# working.net
KiCad netlist of a schematic drawn in EAGLE
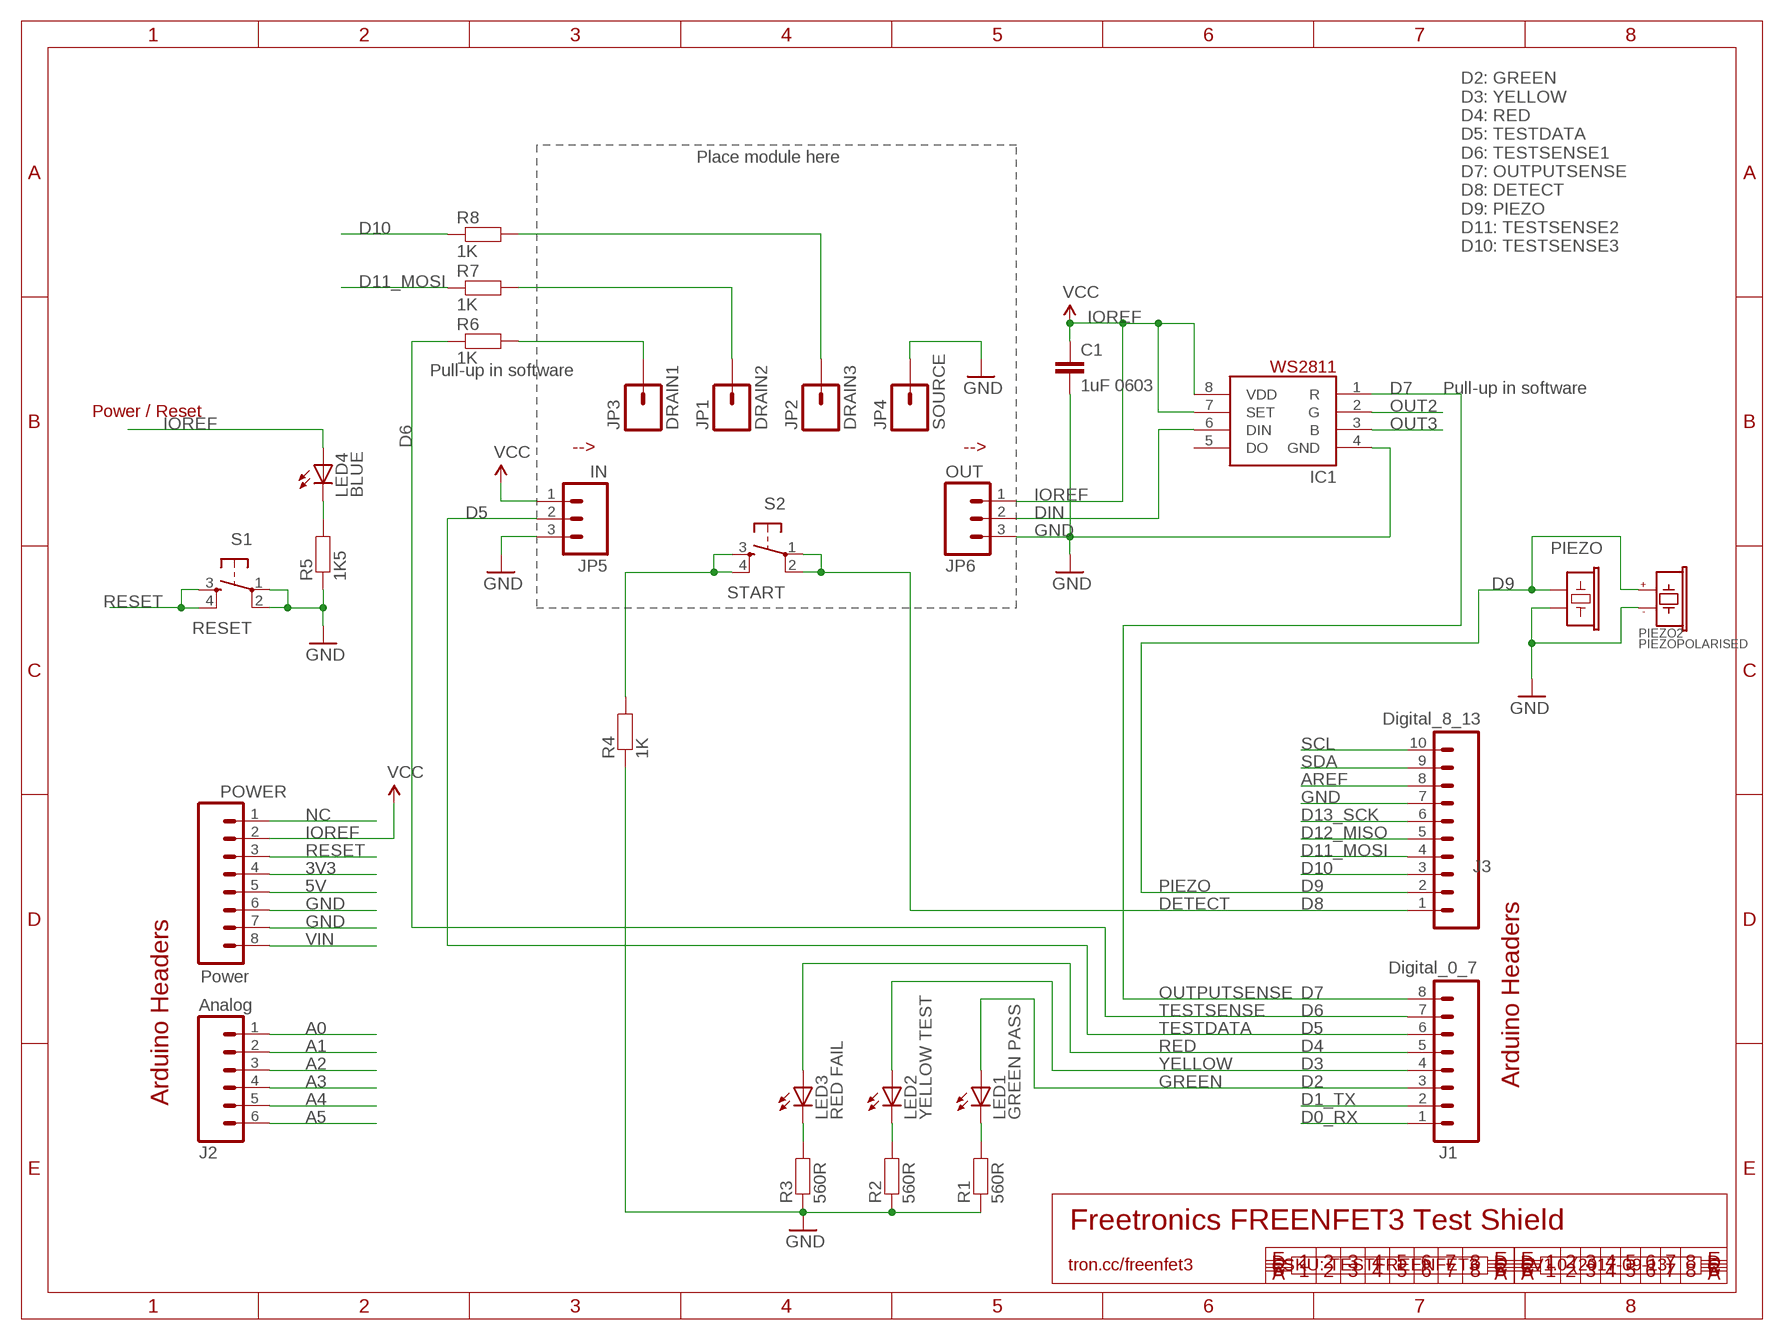
[diagram p0: schematic, sheet 1]

(export (version "E")
  (design (tool "Eeschema 10.0.6"))
  (components
    (comp (ref "C1")
      (value "1uF 0603")
      (footprint "eagle-import:0603")
      (libsource (lib "eagle-import") (part "CAP0603"))
    )
    (comp (ref "IC1")
      (value "WS2811-SOP8")
      (footprint "eagle-import:SO08-SKINNYPADS")
      (libsource (lib "eagle-import") (part "WS2811-SOP8"))
    )
    (comp (ref "J1")
      (value "Digital_0_7")
      (footprint "eagle-import:1X08")
      (libsource (lib "eagle-import") (part "M08"))
    )
    (comp (ref "J2")
      (value "Analog")
      (footprint "eagle-import:1X06")
      (libsource (lib "eagle-import") (part "M06SIP"))
    )
    (comp (ref "J3")
      (value "Digital_8_13")
      (footprint "eagle-import:1X10")
      (libsource (lib "eagle-import") (part "M100.1"))
    )
    (comp (ref "JP1")
      (value "DRAIN2")
      (footprint "eagle-import:1X01_2_1_MM")
      (libsource (lib "eagle-import") (part "M012.1MM"))
    )
    (comp (ref "JP2")
      (value "DRAIN3")
      (footprint "eagle-import:1X01_2_1_MM")
      (libsource (lib "eagle-import") (part "M012.1MM"))
    )
    (comp (ref "JP3")
      (value "DRAIN1")
      (footprint "eagle-import:1X01_2_1_MM")
      (libsource (lib "eagle-import") (part "M012.1MM"))
    )
    (comp (ref "JP4")
      (value "SOURCE")
      (footprint "eagle-import:1X01_2_1_MM")
      (libsource (lib "eagle-import") (part "M012.1MM"))
    )
    (comp (ref "JP5")
      (value "IN")
      (footprint "eagle-import:1X03")
      (libsource (lib "eagle-import") (part "M03PTH"))
    )
    (comp (ref "JP6")
      (value "OUT")
      (footprint "eagle-import:1X03")
      (libsource (lib "eagle-import") (part "M03PTH"))
    )
    (comp (ref "LED1")
      (value "GREEN PASS")
      (footprint "eagle-import:LED-0603")
      (libsource (lib "eagle-import") (part "LED0603"))
    )
    (comp (ref "LED2")
      (value "YELLOW TEST")
      (footprint "eagle-import:LED-0603")
      (libsource (lib "eagle-import") (part "LED0603"))
    )
    (comp (ref "LED3")
      (value "RED FAIL")
      (footprint "eagle-import:LED-0603")
      (libsource (lib "eagle-import") (part "LED0603"))
    )
    (comp (ref "LED4")
      (value "BLUE")
      (footprint "eagle-import:LED-0603")
      (libsource (lib "eagle-import") (part "LED0603"))
    )
    (comp (ref "PIEZO")
      (value "BUZZERSMD12X12")
      (footprint "eagle-import:BUZZER-12X12-SMT")
      (libsource (lib "eagle-import") (part "BUZZERSMD12X12"))
    )
    (comp (ref "PIEZO2")
      (value "PIEZOPOLARISED")
      (footprint "eagle-import:PIEZO12MMWIDEPOLARISED")
      (libsource (lib "eagle-import") (part "PIEZOPOLARISED"))
    )
    (comp (ref "POWER")
      (value "Power")
      (footprint "eagle-import:1X08")
      (libsource (lib "eagle-import") (part "M08"))
    )
    (comp (ref "R1")
      (value "560R")
      (footprint "eagle-import:0603")
      (libsource (lib "eagle-import") (part "RESISTOR0603"))
    )
    (comp (ref "R2")
      (value "560R")
      (footprint "eagle-import:0603")
      (libsource (lib "eagle-import") (part "RESISTOR0603"))
    )
    (comp (ref "R3")
      (value "560R")
      (footprint "eagle-import:0603")
      (libsource (lib "eagle-import") (part "RESISTOR0603"))
    )
    (comp (ref "R4")
      (value "1K")
      (footprint "eagle-import:0603")
      (libsource (lib "eagle-import") (part "RESISTOR0603"))
    )
    (comp (ref "R5")
      (value "1K5")
      (footprint "eagle-import:0603")
      (libsource (lib "eagle-import") (part "RESISTOR0603"))
    )
    (comp (ref "R6")
      (value "1K")
      (footprint "eagle-import:0603")
      (libsource (lib "eagle-import") (part "RESISTOR0603"))
    )
    (comp (ref "R7")
      (value "1K")
      (footprint "eagle-import:0603")
      (libsource (lib "eagle-import") (part "RESISTOR0603"))
    )
    (comp (ref "R8")
      (value "1K")
      (footprint "eagle-import:0603")
      (libsource (lib "eagle-import") (part "RESISTOR0603"))
    )
    (comp (ref "S1")
      (value "RESET")
      (footprint "eagle-import:TACTILE-PTH")
      (libsource (lib "eagle-import") (part "TAC_SWITCHPTH"))
    )
    (comp (ref "S2")
      (value "START")
      (footprint "eagle-import:TACTILE-PTH")
      (libsource (lib "eagle-import") (part "TAC_SWITCHPTH"))
    )
  )
  (nets
    (net (code "1") (name "/3V3") (class "Default")
      (node (ref "POWER") (pin "4") (pinfunction "4_4") (pintype "passive"))
    )
    (net (code "2") (name "/5V") (class "Default")
      (node (ref "POWER") (pin "5") (pinfunction "5_5") (pintype "passive"))
    )
    (net (code "3") (name "/A0") (class "Default")
      (node (ref "J2") (pin "1") (pinfunction "1_1") (pintype "passive"))
    )
    (net (code "4") (name "/A1") (class "Default")
      (node (ref "J2") (pin "2") (pinfunction "2_2") (pintype "passive"))
    )
    (net (code "5") (name "/A2") (class "Default")
      (node (ref "J2") (pin "3") (pinfunction "3_3") (pintype "passive"))
    )
    (net (code "6") (name "/A3") (class "Default")
      (node (ref "J2") (pin "4") (pinfunction "4_4") (pintype "passive"))
    )
    (net (code "7") (name "/A4") (class "Default")
      (node (ref "J2") (pin "5") (pinfunction "5_5") (pintype "passive"))
    )
    (net (code "8") (name "/A5") (class "Default")
      (node (ref "J2") (pin "6") (pinfunction "6_6") (pintype "passive"))
    )
    (net (code "9") (name "/AREF") (class "Default")
      (node (ref "J3") (pin "8") (pinfunction "8_8") (pintype "passive"))
    )
    (net (code "10") (name "/D0_RX") (class "Default")
      (node (ref "J1") (pin "1") (pinfunction "1_1") (pintype "passive"))
    )
    (net (code "11") (name "/D1_TX") (class "Default")
      (node (ref "J1") (pin "2") (pinfunction "2_2") (pintype "passive"))
    )
    (net (code "12") (name "/D2") (class "Default")
      (node (ref "J1") (pin "3") (pinfunction "3_3") (pintype "passive"))
      (node (ref "LED1") (pin "A") (pinfunction "A_A") (pintype "passive"))
    )
    (net (code "13") (name "/D3") (class "Default")
      (node (ref "J1") (pin "4") (pinfunction "4_4") (pintype "passive"))
      (node (ref "LED2") (pin "A") (pinfunction "A_A") (pintype "passive"))
    )
    (net (code "14") (name "/D4") (class "Default")
      (node (ref "J1") (pin "5") (pinfunction "5_5") (pintype "passive"))
      (node (ref "LED3") (pin "A") (pinfunction "A_A") (pintype "passive"))
    )
    (net (code "15") (name "/D5") (class "Default")
      (node (ref "J1") (pin "6") (pinfunction "6_6") (pintype "passive"))
      (node (ref "JP5") (pin "2") (pinfunction "2_2") (pintype "passive"))
    )
    (net (code "16") (name "/D6") (class "Default")
      (node (ref "J1") (pin "7") (pinfunction "7_7") (pintype "passive"))
      (node (ref "R6") (pin "1") (pinfunction "1_1") (pintype "passive"))
    )
    (net (code "17") (name "/D7") (class "Default")
      (node (ref "IC1") (pin "1") (pinfunction "R_1") (pintype "open_collector"))
      (node (ref "J1") (pin "8") (pinfunction "8_8") (pintype "passive"))
    )
    (net (code "18") (name "/D8") (class "Default")
      (node (ref "J3") (pin "1") (pinfunction "1_1") (pintype "passive"))
      (node (ref "S2") (pin "1") (pinfunction "1_1") (pintype "passive"))
      (node (ref "S2") (pin "2") (pinfunction "2_2") (pintype "passive"))
    )
    (net (code "19") (name "/D9") (class "Default")
      (node (ref "J3") (pin "2") (pinfunction "2_2") (pintype "passive"))
      (node (ref "PIEZO") (pin "2") (pinfunction "2_2") (pintype "passive"))
      (node (ref "PIEZO2") (pin "1") (pinfunction "+_1") (pintype "bidirectional"))
    )
    (net (code "20") (name "/D10") (class "Default")
      (node (ref "J3") (pin "3") (pinfunction "3_3") (pintype "passive"))
      (node (ref "R8") (pin "1") (pinfunction "1_1") (pintype "passive"))
    )
    (net (code "21") (name "/D11_MOSI") (class "Default")
      (node (ref "J3") (pin "4") (pinfunction "4_4") (pintype "passive"))
      (node (ref "R7") (pin "1") (pinfunction "1_1") (pintype "passive"))
    )
    (net (code "22") (name "/D12_MISO") (class "Default")
      (node (ref "J3") (pin "5") (pinfunction "5_5") (pintype "passive"))
    )
    (net (code "23") (name "/D13_SCK") (class "Default")
      (node (ref "J3") (pin "6") (pinfunction "6_6") (pintype "passive"))
    )
    (net (code "24") (name "/DIN") (class "Default")
      (node (ref "IC1") (pin "6") (pinfunction "DIN_6") (pintype "input"))
      (node (ref "JP6") (pin "2") (pinfunction "2_2") (pintype "passive"))
    )
    (net (code "25") (name "/NC") (class "Default")
      (node (ref "POWER") (pin "1") (pinfunction "1_1") (pintype "passive"))
    )
    (net (code "26") (name "/OUT2") (class "Default")
      (node (ref "IC1") (pin "2") (pinfunction "G_2") (pintype "open_collector"))
    )
    (net (code "27") (name "/OUT3") (class "Default")
      (node (ref "IC1") (pin "3") (pinfunction "B_3") (pintype "open_collector"))
    )
    (net (code "28") (name "/RESET") (class "Default")
      (node (ref "POWER") (pin "3") (pinfunction "3_3") (pintype "passive"))
      (node (ref "S1") (pin "3") (pinfunction "3_3") (pintype "passive"))
      (node (ref "S1") (pin "4") (pinfunction "4_4") (pintype "passive"))
    )
    (net (code "29") (name "/SCL") (class "Default")
      (node (ref "J3") (pin "10") (pinfunction "10_10") (pintype "passive"))
    )
    (net (code "30") (name "/SDA") (class "Default")
      (node (ref "J3") (pin "9") (pinfunction "9_9") (pintype "passive"))
    )
    (net (code "31") (name "/VIN") (class "Default")
      (node (ref "POWER") (pin "8") (pinfunction "8_8") (pintype "passive"))
    )
    (net (code "32") (name "GND") (class "Default")
      (node (ref "C1") (pin "2") (pinfunction "2_2") (pintype "passive"))
      (node (ref "IC1") (pin "4") (pinfunction "GND_4") (pintype "power_in"))
      (node (ref "J3") (pin "7") (pinfunction "7_7") (pintype "passive"))
      (node (ref "JP4") (pin "1") (pinfunction "1_1") (pintype "passive"))
      (node (ref "JP5") (pin "3") (pinfunction "3_3") (pintype "passive"))
      (node (ref "JP6") (pin "3") (pinfunction "3_3") (pintype "passive"))
      (node (ref "PIEZO") (pin "1") (pinfunction "1_1") (pintype "passive"))
      (node (ref "PIEZO2") (pin "2") (pinfunction "-_2") (pintype "bidirectional"))
      (node (ref "POWER") (pin "6") (pinfunction "6_6") (pintype "passive"))
      (node (ref "POWER") (pin "7") (pinfunction "7_7") (pintype "passive"))
      (node (ref "R1") (pin "1") (pinfunction "1_1") (pintype "passive"))
      (node (ref "R2") (pin "1") (pinfunction "1_1") (pintype "passive"))
      (node (ref "R3") (pin "1") (pinfunction "1_1") (pintype "passive"))
      (node (ref "R4") (pin "1") (pinfunction "1_1") (pintype "passive"))
      (node (ref "R5") (pin "1") (pinfunction "1_1") (pintype "passive"))
      (node (ref "S1") (pin "1") (pinfunction "1_1") (pintype "passive"))
      (node (ref "S1") (pin "2") (pinfunction "2_2") (pintype "passive"))
    )
    (net (code "33") (name "Net-(JP1-Pad1)") (class "Default")
      (node (ref "JP1") (pin "1") (pinfunction "1_1") (pintype "passive"))
      (node (ref "R7") (pin "2") (pinfunction "2_2") (pintype "passive"))
    )
    (net (code "34") (name "Net-(JP2-Pad1)") (class "Default")
      (node (ref "JP2") (pin "1") (pinfunction "1_1") (pintype "passive"))
      (node (ref "R8") (pin "2") (pinfunction "2_2") (pintype "passive"))
    )
    (net (code "35") (name "Net-(JP3-Pad1)") (class "Default")
      (node (ref "JP3") (pin "1") (pinfunction "1_1") (pintype "passive"))
      (node (ref "R6") (pin "2") (pinfunction "2_2") (pintype "passive"))
    )
    (net (code "36") (name "Net-(LED1-PadC)") (class "Default")
      (node (ref "LED1") (pin "C") (pinfunction "C_C") (pintype "passive"))
      (node (ref "R1") (pin "2") (pinfunction "2_2") (pintype "passive"))
    )
    (net (code "37") (name "Net-(LED2-PadC)") (class "Default")
      (node (ref "LED2") (pin "C") (pinfunction "C_C") (pintype "passive"))
      (node (ref "R2") (pin "2") (pinfunction "2_2") (pintype "passive"))
    )
    (net (code "38") (name "Net-(LED3-PadC)") (class "Default")
      (node (ref "LED3") (pin "C") (pinfunction "C_C") (pintype "passive"))
      (node (ref "R3") (pin "2") (pinfunction "2_2") (pintype "passive"))
    )
    (net (code "39") (name "Net-(LED4-PadC)") (class "Default")
      (node (ref "LED4") (pin "C") (pinfunction "C_C") (pintype "passive"))
      (node (ref "R5") (pin "2") (pinfunction "2_2") (pintype "passive"))
    )
    (net (code "40") (name "Net-(R4-Pad2)") (class "Default")
      (node (ref "R4") (pin "2") (pinfunction "2_2") (pintype "passive"))
      (node (ref "S2") (pin "3") (pinfunction "3_3") (pintype "passive"))
      (node (ref "S2") (pin "4") (pinfunction "4_4") (pintype "passive"))
    )
    (net (code "41") (name "VCC") (class "Default")
      (node (ref "C1") (pin "1") (pinfunction "1_1") (pintype "passive"))
      (node (ref "IC1") (pin "7") (pinfunction "SET_7") (pintype "input"))
      (node (ref "IC1") (pin "8") (pinfunction "VDD_8") (pintype "power_in"))
      (node (ref "JP5") (pin "1") (pinfunction "1_1") (pintype "passive"))
      (node (ref "JP6") (pin "1") (pinfunction "1_1") (pintype "passive"))
      (node (ref "LED4") (pin "A") (pinfunction "A_A") (pintype "passive"))
      (node (ref "POWER") (pin "2") (pinfunction "2_2") (pintype "passive"))
    )
    (net (code "42") (name "unconnected-(IC1-DO-Pad5)") (class "Default")
      (node (ref "IC1") (pin "5") (pinfunction "DO_5") (pintype "output"))
    )
  )
)
